# GPSDO_DAC.net
KiCad netlist of a schematic drawn in Altium Designer
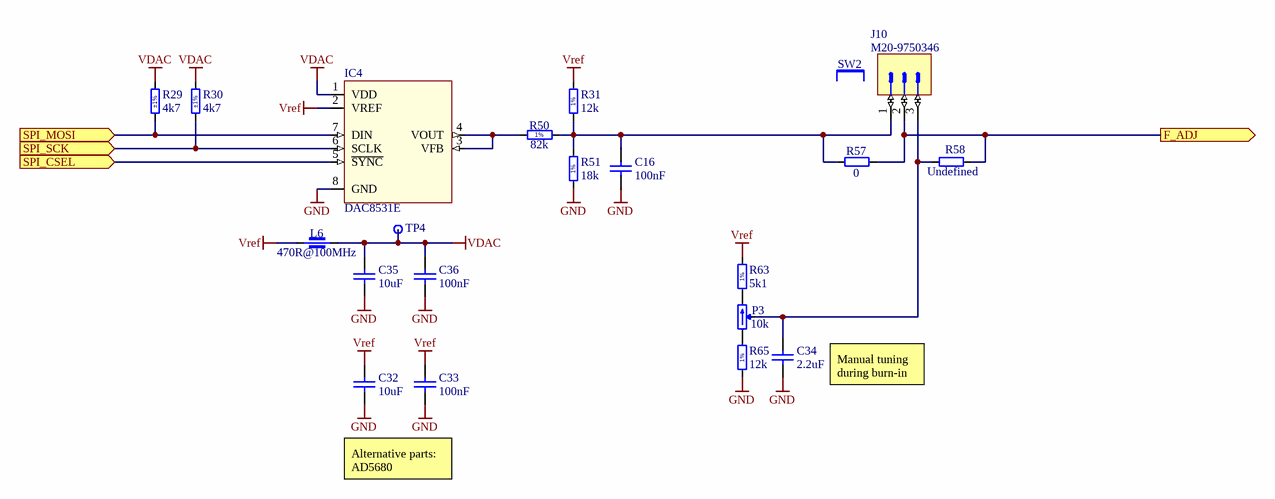
[diagram p0: GPSDO_DAC.SchDoc]

(export (version "E")
  (design (tool "Eeschema 10.0.6"))
  (components
    (comp (ref "C16")
      (value "100nF")
      (footprint "CAPC1005X55N")
      (description "Non-polarised capacitor")
      (fields
        (field (name "PART NUMBER") "CC0402_100NF_16V_10%_X5R")
        (field (name "VOLTAGE") "16V")
        (field (name "AUTHOR") "CERN DEM JLC")
      )
      (libsource (lib "Capacitors") (part "Capacitor - non polarized"))
    )
    (comp (ref "C32")
      (value "10uF")
      (footprint "CAPC1608X80N")
      (description "Non-polarised capacitor")
      (fields
        (field (name "PART NUMBER") "CC0603_10UF_10V_10%_X5R")
        (field (name "VOLTAGE") "10V")
        (field (name "AUTHOR") "CERN DEM JLC")
      )
      (libsource (lib "Capacitors") (part "Capacitor - non polarized"))
    )
    (comp (ref "C33")
      (value "100nF")
      (footprint "CAPC1005X55N")
      (description "Non-polarised capacitor")
      (fields
        (field (name "PART NUMBER") "CC0402_100NF_16V_10%_X5R")
        (field (name "VOLTAGE") "16V")
        (field (name "AUTHOR") "CERN DEM JLC")
      )
      (libsource (lib "Capacitors") (part "Capacitor - non polarized"))
    )
    (comp (ref "C34")
      (value "2.2uF")
      (footprint "CAPC1005X55N")
      (description "Non-polarised capacitor")
      (fields
        (field (name "PART NUMBER") "CC0402_2.2UF_16V_10%_X5R")
        (field (name "VOLTAGE") "16V")
        (field (name "AUTHOR") "CERN DEM BC")
      )
      (libsource (lib "Capacitors") (part "Capacitor - non polarized"))
    )
    (comp (ref "C35")
      (value "10uF")
      (footprint "CAPC1608X80N")
      (description "Non-polarised capacitor")
      (fields
        (field (name "PART NUMBER") "CC0603_10UF_10V_10%_X5R")
        (field (name "VOLTAGE") "10V")
        (field (name "AUTHOR") "CERN DEM JLC")
      )
      (libsource (lib "Capacitors") (part "Capacitor - non polarized"))
    )
    (comp (ref "C36")
      (value "100nF")
      (footprint "CAPC1005X55N")
      (description "Non-polarised capacitor")
      (fields
        (field (name "PART NUMBER") "CC0402_100NF_16V_10%_X5R")
        (field (name "VOLTAGE") "16V")
        (field (name "AUTHOR") "CERN DEM JLC")
      )
      (libsource (lib "Capacitors") (part "Capacitor - non polarized"))
    )
    (comp (ref "IC4")
      (value "DAC8531E")
      (footprint "MSOP-8")
      (description "DAC")
      (fields
        (field (name "MANUFACTURER") "Texas Instruments")
        (field (name "MANUFACTURER PART NUMBER") "DAC8531E/2K5")
      )
      (libsource (lib "Lib") (part "DAC8531E"))
    )
    (comp (ref "J10")
      (value "M20-9750346")
      (footprint "HARWIN_M20-9750346")
      (description "Connector 3 Male 2.54mm")
      (fields (field (name "MANUFACTURER") "Harwin"))
      (libsource (lib "Connectors") (part "Connector 3 Male_1"))
    )
    (comp (ref "L6")
      (value "470R@100MHz")
      (footprint "INDC1608X95N")
      (fields
        (field (name "PART NUMBER") "IND0603_MURATA_BLM18PG471SN1D")
        (field (name "POWER") "1A")
        (field (name "TOLERANCE") "±25%")
        (field (name "AUTHOR") "CERN DEM BC")
      )
      (libsource (lib "Inductors & Transformers") (part "Ferrite Bead"))
    )
    (comp (ref "P3")
      (value "10k")
      (footprint "TRIM_BOURNS_3223W")
      (description "Trimming Potentiometer")
      (fields
        (field (name "PART NUMBER") "TRIM_11T_10K_BOURNS_3223W-1-103E")
        (field (name "POWER") "0.125W")
        (field (name "AUTHOR") "CERN DEM JLC")
      )
      (libsource (lib "Resistors") (part "Trimming Potentiometer"))
    )
    (comp (ref "R29")
      (value "4k7")
      (footprint "RESC1005X40N")
      (description "Resistor - 1%")
      (fields
        (field (name "TOLERANCE") "±1%")
        (field (name "PART NUMBER") "R0402_4K7_1%_0.0625W_100PPM")
        (field (name "POWER") "0.0625W")
        (field (name "AUTHOR") "CERN DEM JLC")
      )
      (libsource (lib "Resistors") (part "Resistor - 1%"))
    )
    (comp (ref "R30")
      (value "4k7")
      (footprint "RESC1005X40N")
      (description "Resistor - 1%")
      (fields
        (field (name "TOLERANCE") "±1%")
        (field (name "PART NUMBER") "R0402_4K7_1%_0.0625W_100PPM")
        (field (name "POWER") "0.0625W")
        (field (name "AUTHOR") "CERN DEM JLC")
      )
      (libsource (lib "Resistors") (part "Resistor - 1%"))
    )
    (comp (ref "R31")
      (value "12k")
      (footprint "RESC1005X40N")
      (description "Resistor - 1%")
      (fields
        (field (name "PART NUMBER") "R0402_12K_1%_0.0625W_100PPM")
        (field (name "POWER") "0.0625W")
        (field (name "AUTHOR") "CERN DEM JLC")
      )
      (libsource (lib "Resistors") (part "Resistor - 1%"))
    )
    (comp (ref "R50")
      (value "82k")
      (footprint "RESC1005X40N")
      (description "Resistor - 1%")
      (fields
        (field (name "PART NUMBER") "R0402_82K_1%_0.0625W_100PPM")
        (field (name "POWER") "0.0625W")
        (field (name "AUTHOR") "CERN DEM JLC")
      )
      (libsource (lib "Resistors") (part "Resistor - 1%"))
    )
    (comp (ref "R51")
      (value "18k")
      (footprint "RESC1005X40N")
      (description "Resistor - 1%")
      (fields
        (field (name "PART NUMBER") "R0402_18K_1%_0.0625W_100PPM")
        (field (name "POWER") "0.0625W")
        (field (name "AUTHOR") "CERN DEM JLC")
      )
      (libsource (lib "Resistors") (part "Resistor - 1%"))
    )
    (comp (ref "R57")
      (value "0")
      (footprint "RESC1005X40N")
      (description "Resistor")
      (fields
        (field (name "PART NUMBER") "R0402_0R_JUMPER")
        (field (name "MANUFACTURER") "GENERIC")
        (field (name "AUTHOR") "CERN DEM JLC")
      )
      (libsource (lib "Resistors") (part "Resistor"))
    )
    (comp (ref "R58")
      (value "Undefined")
      (footprint "RESC1005X40N")
      (description "Resistor")
      (fields (field (name "PART NUMBER") "R0402_NO-VALUE") (field (name "AUTHOR") "CERN DEM JLC"))
      (libsource (lib "Resistors") (part "Resistor"))
    )
    (comp (ref "R63")
      (value "5k1")
      (footprint "RESC1005X40N")
      (description "Resistor - 1%")
      (fields
        (field (name "PART NUMBER") "R0402_5K1_1%_0.0625W_100PPM")
        (field (name "POWER") "0.0625W")
        (field (name "AUTHOR") "CERN DEM JLC")
      )
      (libsource (lib "Resistors") (part "Resistor - 1%"))
    )
    (comp (ref "R65")
      (value "12k")
      (footprint "RESC1005X40N")
      (description "Resistor - 1%")
      (fields
        (field (name "PART NUMBER") "R0402_12K_1%_0.0625W_100PPM")
        (field (name "POWER") "0.0625W")
        (field (name "AUTHOR") "CERN DEM JLC")
      )
      (libsource (lib "Resistors") (part "Resistor - 1%"))
    )
    (comp (ref "SW2")
      (value "M7582-46")
      (footprint "HARWIN_M7582-46")
      (description "Jumper 1 Pin")
      (fields (field (name "MANUFACTURER") "Harwin"))
      (libsource (lib "Connectors") (part "HARWIN_M7582-46"))
    )
    (comp (ref "TP4")
      (value "Test Point")
      (footprint "TPS127")
      (fields (field (name "PART NUMBER") "SMD_PAD_1.27X1.27MM") (field (name "AUTHOR") "CERN DEM JLC"))
      (libsource (lib "Eletro-mechanical") (part "Test Point"))
    )
  )
  (nets
    (net (code "1") (name "/F_ADJ") (class "Default")
      (node (ref "J10") (pin "2") (pinfunction "2_2") (pintype "bidirectional"))
      (node (ref "R57") (pin "1") (pinfunction "1_1") (pintype "passive"))
      (node (ref "R58") (pin "2") (pinfunction "2_2") (pintype "passive"))
    )
    (net (code "2") (name "/SPI_CSEL") (class "Default")
      (node (ref "IC4") (pin "5") (pinfunction "~{SYNC}_5") (pintype "input"))
    )
    (net (code "3") (name "/SPI_MOSI") (class "Default")
      (node (ref "IC4") (pin "7") (pinfunction "DIN_7") (pintype "input"))
      (node (ref "R29") (pin "1") (pinfunction "1_1") (pintype "passive"))
    )
    (net (code "4") (name "/SPI_SCK") (class "Default")
      (node (ref "IC4") (pin "6") (pinfunction "SCLK_6") (pintype "input"))
      (node (ref "R30") (pin "1") (pinfunction "1_1") (pintype "passive"))
    )
    (net (code "5") (name "GND") (class "Default")
      (node (ref "C16") (pin "1") (pinfunction "1_1") (pintype "passive"))
      (node (ref "C32") (pin "1") (pinfunction "1_1") (pintype "passive"))
      (node (ref "C33") (pin "1") (pinfunction "1_1") (pintype "passive"))
      (node (ref "C34") (pin "1") (pinfunction "1_1") (pintype "passive"))
      (node (ref "C35") (pin "1") (pinfunction "1_1") (pintype "passive"))
      (node (ref "C36") (pin "1") (pinfunction "1_1") (pintype "passive"))
      (node (ref "IC4") (pin "8") (pinfunction "GND_8") (pintype "power_in"))
      (node (ref "R51") (pin "1") (pinfunction "1_1") (pintype "passive"))
      (node (ref "R65") (pin "1") (pinfunction "1_1") (pintype "passive"))
    )
    (net (code "6") (name "Net-(C16-Pad2)") (class "Default")
      (node (ref "C16") (pin "2") (pinfunction "2_2") (pintype "passive"))
      (node (ref "J10") (pin "1") (pinfunction "1_1") (pintype "bidirectional"))
      (node (ref "R31") (pin "1") (pinfunction "1_1") (pintype "passive"))
      (node (ref "R50") (pin "2") (pinfunction "2_2") (pintype "passive"))
      (node (ref "R51") (pin "2") (pinfunction "2_2") (pintype "passive"))
      (node (ref "R57") (pin "2") (pinfunction "2_2") (pintype "passive"))
    )
    (net (code "7") (name "Net-(IC4-VFB)") (class "Default")
      (node (ref "IC4") (pin "3") (pinfunction "VFB_3") (pintype "input"))
      (node (ref "IC4") (pin "4") (pinfunction "VOUT_4") (pintype "output"))
      (node (ref "R50") (pin "1") (pinfunction "1_1") (pintype "passive"))
    )
    (net (code "8") (name "Net-(P3-CCW)") (class "Default")
      (node (ref "P3") (pin "1") (pinfunction "CCW_1") (pintype "passive"))
      (node (ref "R65") (pin "2") (pinfunction "2_2") (pintype "passive"))
    )
    (net (code "9") (name "Net-(P3-CW)") (class "Default")
      (node (ref "P3") (pin "3") (pinfunction "CW_3") (pintype "passive"))
      (node (ref "R63") (pin "1") (pinfunction "1_1") (pintype "passive"))
    )
    (net (code "10") (name "Net-(P3-W)") (class "Default")
      (node (ref "C34") (pin "2") (pinfunction "2_2") (pintype "passive"))
      (node (ref "J10") (pin "3") (pinfunction "3_3") (pintype "bidirectional"))
      (node (ref "P3") (pin "2") (pinfunction "W_2") (pintype "passive"))
      (node (ref "R58") (pin "1") (pinfunction "1_1") (pintype "passive"))
    )
    (net (code "11") (name "VDAC") (class "Default")
      (node (ref "C35") (pin "2") (pinfunction "2_2") (pintype "passive"))
      (node (ref "C36") (pin "2") (pinfunction "2_2") (pintype "passive"))
      (node (ref "IC4") (pin "1") (pinfunction "VDD_1") (pintype "power_in"))
      (node (ref "L6") (pin "2") (pinfunction "2_2") (pintype "passive"))
      (node (ref "R29") (pin "2") (pinfunction "2_2") (pintype "passive"))
      (node (ref "R30") (pin "2") (pinfunction "2_2") (pintype "passive"))
      (node (ref "TP4") (pin "1") (pinfunction "1_1") (pintype "bidirectional"))
    )
    (net (code "12") (name "Vref") (class "Default")
      (node (ref "C32") (pin "2") (pinfunction "2_2") (pintype "passive"))
      (node (ref "C33") (pin "2") (pinfunction "2_2") (pintype "passive"))
      (node (ref "IC4") (pin "2") (pinfunction "VREF_2") (pintype "power_in"))
      (node (ref "L6") (pin "1") (pinfunction "1_1") (pintype "passive"))
      (node (ref "R31") (pin "2") (pinfunction "2_2") (pintype "passive"))
      (node (ref "R63") (pin "2") (pinfunction "2_2") (pintype "passive"))
    )
    (net (code "13") (name "unconnected-(SW2-Pad1)") (class "Default")
      (node (ref "SW2") (pin "1") (pinfunction "1_1") (pintype "bidirectional"))
    )
  )
)
